# LCDTFT_CTRL_FT813.net
KiCad netlist of a schematic drawn in Altium Designer
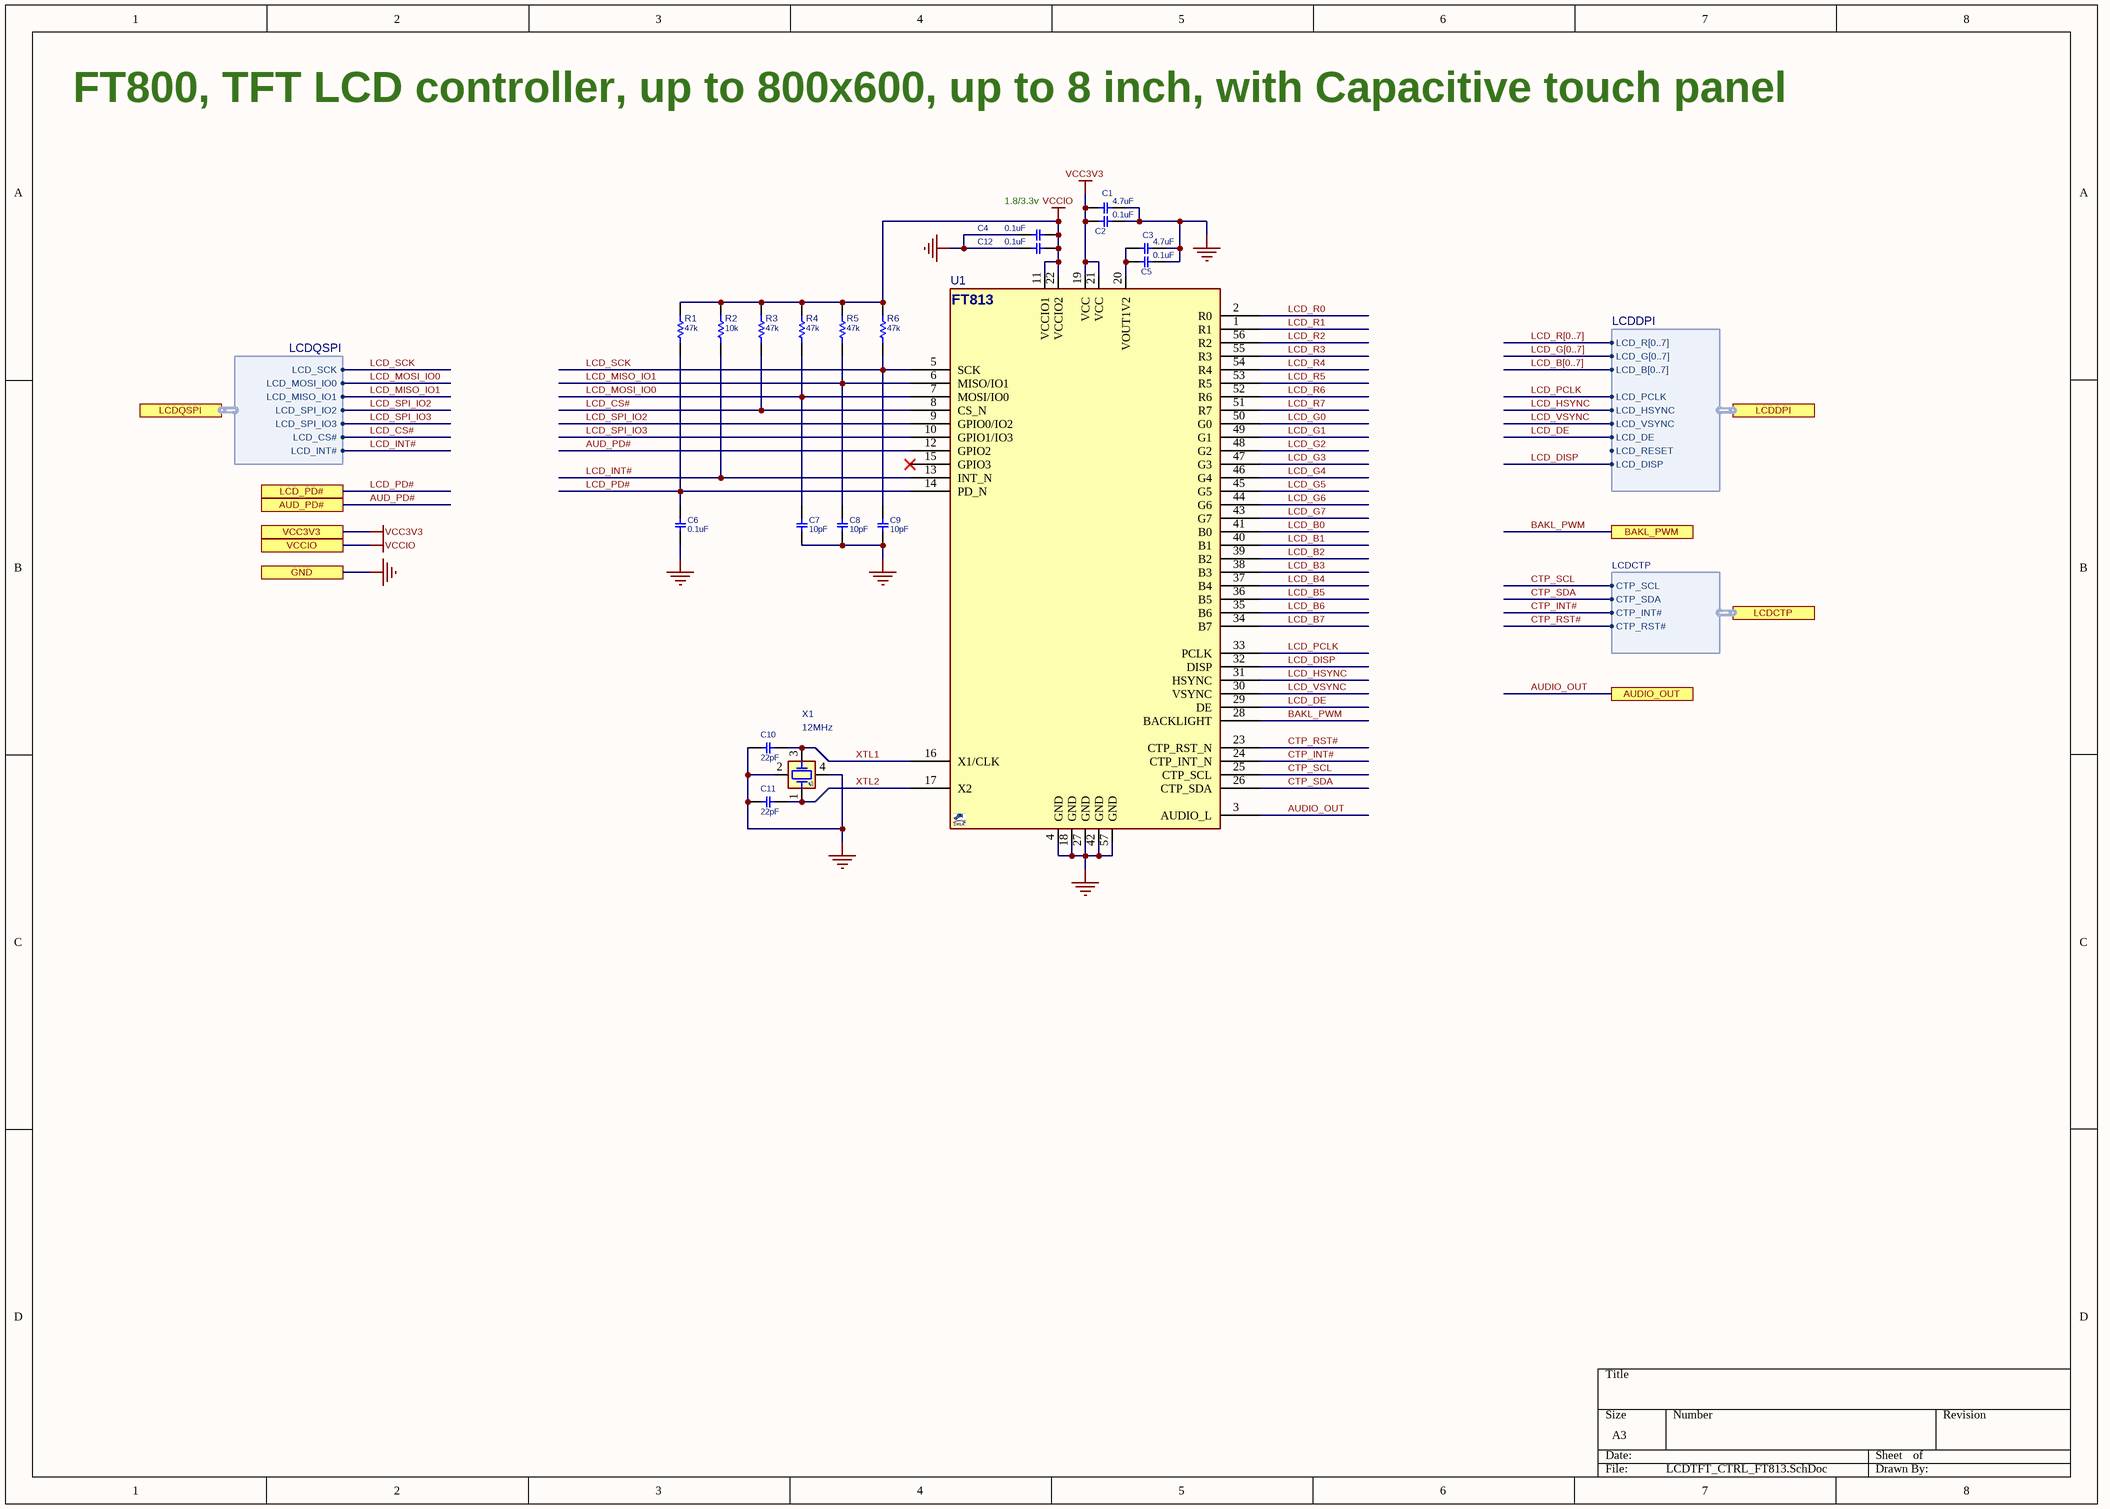
[diagram p0: LCDTFT_CTRL_FT813.SchDoc]

(export (version "E")
  (design (tool "Eeschema 10.0.6"))
  (components
    (comp (ref "C1")
      (value "4.7uF")
      (footprint "C0603")
      (description "CAP, MLCC")
      (libsource (lib "passive_smd") (part "CAP_SMD_MLCC"))
    )
    (comp (ref "C2")
      (value "0.1uF")
      (footprint "C0402")
      (description "CAP, MLCC")
      (fields (field (name "MANF_P#") "GRM155R71H104KE14D") (field (name "MANF") "Murata"))
      (libsource (lib "passive_smd") (part "CAP_SMD_MLCC"))
    )
    (comp (ref "C3")
      (value "4.7uF")
      (footprint "C0603")
      (description "CAP, MLCC")
      (libsource (lib "passive_smd") (part "CAP_SMD_MLCC"))
    )
    (comp (ref "C4")
      (value "0.1uF")
      (footprint "C0402")
      (description "CAP, MLCC")
      (fields (field (name "MANF_P#") "GRM155R71H104KE14D") (field (name "MANF") "Murata"))
      (libsource (lib "passive_smd") (part "CAP_SMD_MLCC"))
    )
    (comp (ref "C5")
      (value "0.1uF")
      (footprint "C0402")
      (description "CAP, MLCC")
      (fields (field (name "MANF_P#") "GRM155R71H104KE14D") (field (name "MANF") "Murata"))
      (libsource (lib "passive_smd") (part "CAP_SMD_MLCC"))
    )
    (comp (ref "C6")
      (value "0.1uF")
      (footprint "C0402")
      (description "CAP, MLCC")
      (fields (field (name "MANF_P#") "GRM155R71H104KE14D") (field (name "MANF") "Murata"))
      (libsource (lib "passive_smd") (part "CAP_SMD_MLCC"))
    )
    (comp (ref "C7")
      (value "10pF")
      (footprint "C0402")
      (description "CAP, MLCC")
      (libsource (lib "passive_smd") (part "CAP_SMD_MLCC"))
    )
    (comp (ref "C8")
      (value "10pF")
      (footprint "C0402")
      (description "CAP, MLCC")
      (libsource (lib "passive_smd") (part "CAP_SMD_MLCC"))
    )
    (comp (ref "C9")
      (value "10pF")
      (footprint "C0402")
      (description "CAP, MLCC")
      (libsource (lib "passive_smd") (part "CAP_SMD_MLCC"))
    )
    (comp (ref "C10")
      (value "22pF")
      (footprint "C0402")
      (description "CAP, MLCC")
      (libsource (lib "passive_smd") (part "CAP_SMD_MLCC"))
    )
    (comp (ref "C11")
      (value "22pF")
      (footprint "C0402")
      (description "CAP, MLCC")
      (libsource (lib "passive_smd") (part "CAP_SMD_MLCC"))
    )
    (comp (ref "C12")
      (value "0.1uF")
      (footprint "C0402")
      (description "CAP, MLCC")
      (fields (field (name "MANF_P#") "GRM155R71H104KE14D") (field (name "MANF") "Murata"))
      (libsource (lib "passive_smd") (part "CAP_SMD_MLCC"))
    )
    (comp (ref "R1")
      (value "47k")
      (footprint "R0402")
      (description "RESISTOR, SMD")
      (libsource (lib "passive_res_smd") (part "RES_SMD"))
    )
    (comp (ref "R2")
      (value "10k")
      (footprint "R0402")
      (description "RESISTOR, SMD")
      (libsource (lib "passive_res_smd") (part "RES_SMD"))
    )
    (comp (ref "R3")
      (value "47k")
      (footprint "R0402")
      (description "RESISTOR, SMD")
      (libsource (lib "passive_res_smd") (part "RES_SMD"))
    )
    (comp (ref "R4")
      (value "47k")
      (footprint "R0402")
      (description "RESISTOR, SMD")
      (libsource (lib "passive_res_smd") (part "RES_SMD"))
    )
    (comp (ref "R5")
      (value "47k")
      (footprint "R0402")
      (description "RESISTOR, SMD")
      (libsource (lib "passive_res_smd") (part "RES_SMD"))
    )
    (comp (ref "R6")
      (value "47k")
      (footprint "R0402")
      (description "RESISTOR, SMD")
      (libsource (lib "passive_res_smd") (part "RES_SMD"))
    )
    (comp (ref "U1")
      (value "FT813")
      (footprint "QFN50_56T")
      (description "LCD Display Controller, Embedded Video Engine, QFN-56")
      (fields (field (name "MANF") "FTDI/Bridgetek") (field (name "MANF_P#") "FT813Q"))
      (libsource (lib "lcdtft_controller") (part "FT813_QFN56"))
    )
    (comp (ref "X1")
      (value "12MHz")
      (footprint "XTL_4_3225")
      (description "Crystal 12MHz")
      (fields (field (name "MANF") "ECS") (field (name "MANF_P#") "ECS-120-18-33-JEM-TR"))
      (libsource (lib "crystal") (part "XTL_4_12MHz_3225"))
    )
  )
  (nets
    (net (code "4") (name "/AUDIO_OUT") (class "Default")
      (node (ref "U1") (pin "3") (pinfunction "AUDIO_L_3") (pintype "passive"))
    )
    (net (code "5") (name "/AUD_PD#") (class "Default")
      (node (ref "U1") (pin "12") (pinfunction "GPIO2_12") (pintype "passive"))
    )
    (net (code "6") (name "/BAKL_PWM") (class "Default")
      (node (ref "U1") (pin "28") (pinfunction "BACKLIGHT_28") (pintype "passive"))
    )
    (net (code "7") (name "/CTP_INT#") (class "Default")
      (node (ref "U1") (pin "24") (pinfunction "CTP_INT_N_24") (pintype "passive"))
    )
    (net (code "8") (name "/CTP_RST#") (class "Default")
      (node (ref "U1") (pin "23") (pinfunction "CTP_RST_N_23") (pintype "passive"))
    )
    (net (code "9") (name "/CTP_SCL") (class "Default")
      (node (ref "U1") (pin "25") (pinfunction "CTP_SCL_25") (pintype "passive"))
    )
    (net (code "10") (name "/CTP_SDA") (class "Default")
      (node (ref "U1") (pin "26") (pinfunction "CTP_SDA_26") (pintype "passive"))
    )
    (net (code "12") (name "/LCD_B0") (class "Default")
      (node (ref "U1") (pin "41") (pinfunction "B0_41") (pintype "passive"))
    )
    (net (code "13") (name "/LCD_B1") (class "Default")
      (node (ref "U1") (pin "40") (pinfunction "B1_40") (pintype "passive"))
    )
    (net (code "14") (name "/LCD_B2") (class "Default")
      (node (ref "U1") (pin "39") (pinfunction "B2_39") (pintype "passive"))
    )
    (net (code "15") (name "/LCD_B3") (class "Default")
      (node (ref "U1") (pin "38") (pinfunction "B3_38") (pintype "passive"))
    )
    (net (code "16") (name "/LCD_B4") (class "Default")
      (node (ref "U1") (pin "37") (pinfunction "B4_37") (pintype "passive"))
    )
    (net (code "17") (name "/LCD_B5") (class "Default")
      (node (ref "U1") (pin "36") (pinfunction "B5_36") (pintype "passive"))
    )
    (net (code "18") (name "/LCD_B6") (class "Default")
      (node (ref "U1") (pin "35") (pinfunction "B6_35") (pintype "passive"))
    )
    (net (code "19") (name "/LCD_B7") (class "Default")
      (node (ref "U1") (pin "34") (pinfunction "B7_34") (pintype "passive"))
    )
    (net (code "21") (name "/LCD_CS#") (class "Default")
      (node (ref "R3") (pin "2") (pinfunction "2_2") (pintype "passive"))
      (node (ref "U1") (pin "8") (pinfunction "CS_N_8") (pintype "passive"))
    )
    (net (code "22") (name "/LCD_DE") (class "Default")
      (node (ref "U1") (pin "29") (pinfunction "DE_29") (pintype "passive"))
    )
    (net (code "23") (name "/LCD_DISP") (class "Default")
      (node (ref "U1") (pin "32") (pinfunction "DISP_32") (pintype "passive"))
    )
    (net (code "24") (name "/LCD_G0") (class "Default")
      (node (ref "U1") (pin "50") (pinfunction "G0_50") (pintype "passive"))
    )
    (net (code "25") (name "/LCD_G1") (class "Default")
      (node (ref "U1") (pin "49") (pinfunction "G1_49") (pintype "passive"))
    )
    (net (code "26") (name "/LCD_G2") (class "Default")
      (node (ref "U1") (pin "48") (pinfunction "G2_48") (pintype "passive"))
    )
    (net (code "27") (name "/LCD_G3") (class "Default")
      (node (ref "U1") (pin "47") (pinfunction "G3_47") (pintype "passive"))
    )
    (net (code "28") (name "/LCD_G4") (class "Default")
      (node (ref "U1") (pin "46") (pinfunction "G4_46") (pintype "passive"))
    )
    (net (code "29") (name "/LCD_G5") (class "Default")
      (node (ref "U1") (pin "45") (pinfunction "G5_45") (pintype "passive"))
    )
    (net (code "30") (name "/LCD_G6") (class "Default")
      (node (ref "U1") (pin "44") (pinfunction "G6_44") (pintype "passive"))
    )
    (net (code "31") (name "/LCD_G7") (class "Default")
      (node (ref "U1") (pin "43") (pinfunction "G7_43") (pintype "passive"))
    )
    (net (code "33") (name "/LCD_HSYNC") (class "Default")
      (node (ref "U1") (pin "31") (pinfunction "HSYNC_31") (pintype "passive"))
    )
    (net (code "34") (name "/LCD_INT#") (class "Default")
      (node (ref "R2") (pin "2") (pinfunction "2_2") (pintype "passive"))
      (node (ref "U1") (pin "13") (pinfunction "INT_N_13") (pintype "passive"))
    )
    (net (code "35") (name "/LCD_MISO_IO1") (class "Default")
      (node (ref "C8") (pin "1") (pinfunction "1_1") (pintype "passive"))
      (node (ref "R5") (pin "2") (pinfunction "2_2") (pintype "passive"))
      (node (ref "U1") (pin "6") (pinfunction "MISO/IO1_6") (pintype "passive"))
    )
    (net (code "36") (name "/LCD_MOSI_IO0") (class "Default")
      (node (ref "C7") (pin "1") (pinfunction "1_1") (pintype "passive"))
      (node (ref "R4") (pin "2") (pinfunction "2_2") (pintype "passive"))
      (node (ref "U1") (pin "7") (pinfunction "MOSI/IO0_7") (pintype "passive"))
    )
    (net (code "37") (name "/LCD_PCLK") (class "Default")
      (node (ref "U1") (pin "33") (pinfunction "PCLK_33") (pintype "passive"))
    )
    (net (code "38") (name "/LCD_PD#") (class "Default")
      (node (ref "C6") (pin "1") (pinfunction "1_1") (pintype "passive"))
      (node (ref "R1") (pin "2") (pinfunction "2_2") (pintype "passive"))
      (node (ref "U1") (pin "14") (pinfunction "PD_N_14") (pintype "passive"))
    )
    (net (code "39") (name "/LCD_R0") (class "Default")
      (node (ref "U1") (pin "2") (pinfunction "R0_2") (pintype "passive"))
    )
    (net (code "40") (name "/LCD_R1") (class "Default")
      (node (ref "U1") (pin "1") (pinfunction "R1_1") (pintype "passive"))
    )
    (net (code "41") (name "/LCD_R2") (class "Default")
      (node (ref "U1") (pin "56") (pinfunction "R2_56") (pintype "passive"))
    )
    (net (code "42") (name "/LCD_R3") (class "Default")
      (node (ref "U1") (pin "55") (pinfunction "R3_55") (pintype "passive"))
    )
    (net (code "43") (name "/LCD_R4") (class "Default")
      (node (ref "U1") (pin "54") (pinfunction "R4_54") (pintype "passive"))
    )
    (net (code "44") (name "/LCD_R5") (class "Default")
      (node (ref "U1") (pin "53") (pinfunction "R5_53") (pintype "passive"))
    )
    (net (code "45") (name "/LCD_R6") (class "Default")
      (node (ref "U1") (pin "52") (pinfunction "R6_52") (pintype "passive"))
    )
    (net (code "46") (name "/LCD_R7") (class "Default")
      (node (ref "U1") (pin "51") (pinfunction "R7_51") (pintype "passive"))
    )
    (net (code "47") (name "/LCD_SCK") (class "Default")
      (node (ref "C9") (pin "1") (pinfunction "1_1") (pintype "passive"))
      (node (ref "R6") (pin "2") (pinfunction "2_2") (pintype "passive"))
      (node (ref "U1") (pin "5") (pinfunction "SCK_5") (pintype "passive"))
    )
    (net (code "48") (name "/LCD_SPI_IO2") (class "Default")
      (node (ref "U1") (pin "9") (pinfunction "GPIO0/IO2_9") (pintype "passive"))
    )
    (net (code "49") (name "/LCD_SPI_IO3") (class "Default")
      (node (ref "U1") (pin "10") (pinfunction "GPIO1/IO3_10") (pintype "passive"))
    )
    (net (code "50") (name "/LCD_VSYNC") (class "Default")
      (node (ref "U1") (pin "30") (pinfunction "VSYNC_30") (pintype "passive"))
    )
    (net (code "51") (name "/XTL1") (class "Default")
      (node (ref "C10") (pin "2") (pinfunction "2_2") (pintype "passive"))
      (node (ref "U1") (pin "16") (pinfunction "X1/CLK_16") (pintype "passive"))
      (node (ref "X1") (pin "3") (pinfunction "2_3") (pintype "passive"))
    )
    (net (code "52") (name "/XTL2") (class "Default")
      (node (ref "C11") (pin "1") (pinfunction "1_1") (pintype "passive"))
      (node (ref "U1") (pin "17") (pinfunction "X2_17") (pintype "passive"))
      (node (ref "X1") (pin "1") (pinfunction "1_1") (pintype "passive"))
    )
    (net (code "56") (name "GND") (class "Default")
      (node (ref "C1") (pin "1") (pinfunction "1_1") (pintype "passive"))
      (node (ref "C10") (pin "1") (pinfunction "1_1") (pintype "passive"))
      (node (ref "C11") (pin "2") (pinfunction "2_2") (pintype "passive"))
      (node (ref "C12") (pin "2") (pinfunction "2_2") (pintype "passive"))
      (node (ref "C2") (pin "1") (pinfunction "1_1") (pintype "passive"))
      (node (ref "C3") (pin "1") (pinfunction "1_1") (pintype "passive"))
      (node (ref "C4") (pin "2") (pinfunction "2_2") (pintype "passive"))
      (node (ref "C5") (pin "1") (pinfunction "1_1") (pintype "passive"))
      (node (ref "C6") (pin "2") (pinfunction "2_2") (pintype "passive"))
      (node (ref "C7") (pin "2") (pinfunction "2_2") (pintype "passive"))
      (node (ref "C8") (pin "2") (pinfunction "2_2") (pintype "passive"))
      (node (ref "C9") (pin "2") (pinfunction "2_2") (pintype "passive"))
      (node (ref "U1") (pin "18") (pinfunction "GND_18") (pintype "passive"))
      (node (ref "U1") (pin "27") (pinfunction "GND_27") (pintype "passive"))
      (node (ref "U1") (pin "4") (pinfunction "GND_4") (pintype "passive"))
      (node (ref "U1") (pin "42") (pinfunction "GND_42") (pintype "passive"))
      (node (ref "U1") (pin "57") (pinfunction "GND_57") (pintype "passive"))
      (node (ref "X1") (pin "2") (pinfunction "2_2") (pintype "passive"))
      (node (ref "X1") (pin "4") (pinfunction "4_4") (pintype "passive"))
    )
    (net (code "57") (name "Net-(U1-VOUT1V2)") (class "Default")
      (node (ref "C3") (pin "2") (pinfunction "2_2") (pintype "passive"))
      (node (ref "C5") (pin "2") (pinfunction "2_2") (pintype "passive"))
      (node (ref "U1") (pin "20") (pinfunction "VOUT1V2_20") (pintype "passive"))
    )
    (net (code "58") (name "VCC3V3") (class "Default")
      (node (ref "C1") (pin "2") (pinfunction "2_2") (pintype "passive"))
      (node (ref "C2") (pin "2") (pinfunction "2_2") (pintype "passive"))
      (node (ref "U1") (pin "19") (pinfunction "VCC_19") (pintype "passive"))
      (node (ref "U1") (pin "21") (pinfunction "VCC_21") (pintype "passive"))
    )
    (net (code "59") (name "VCCIO") (class "Default")
      (node (ref "C12") (pin "1") (pinfunction "1_1") (pintype "passive"))
      (node (ref "C4") (pin "1") (pinfunction "1_1") (pintype "passive"))
      (node (ref "R1") (pin "1") (pinfunction "1_1") (pintype "passive"))
      (node (ref "R2") (pin "1") (pinfunction "1_1") (pintype "passive"))
      (node (ref "R3") (pin "1") (pinfunction "1_1") (pintype "passive"))
      (node (ref "R4") (pin "1") (pinfunction "1_1") (pintype "passive"))
      (node (ref "R5") (pin "1") (pinfunction "1_1") (pintype "passive"))
      (node (ref "R6") (pin "1") (pinfunction "1_1") (pintype "passive"))
      (node (ref "U1") (pin "11") (pinfunction "VCCIO1_11") (pintype "passive"))
      (node (ref "U1") (pin "22") (pinfunction "VCCIO2_22") (pintype "passive"))
    )
    (net (code "60") (name "unconnected-(U1-GPIO3-Pad15)") (class "Default")
      (node (ref "U1") (pin "15") (pinfunction "GPIO3_15") (pintype "passive+no_connect"))
    )
  )
)
